# RoboSim_top_level.net
KiCad netlist of a schematic drawn in EAGLE
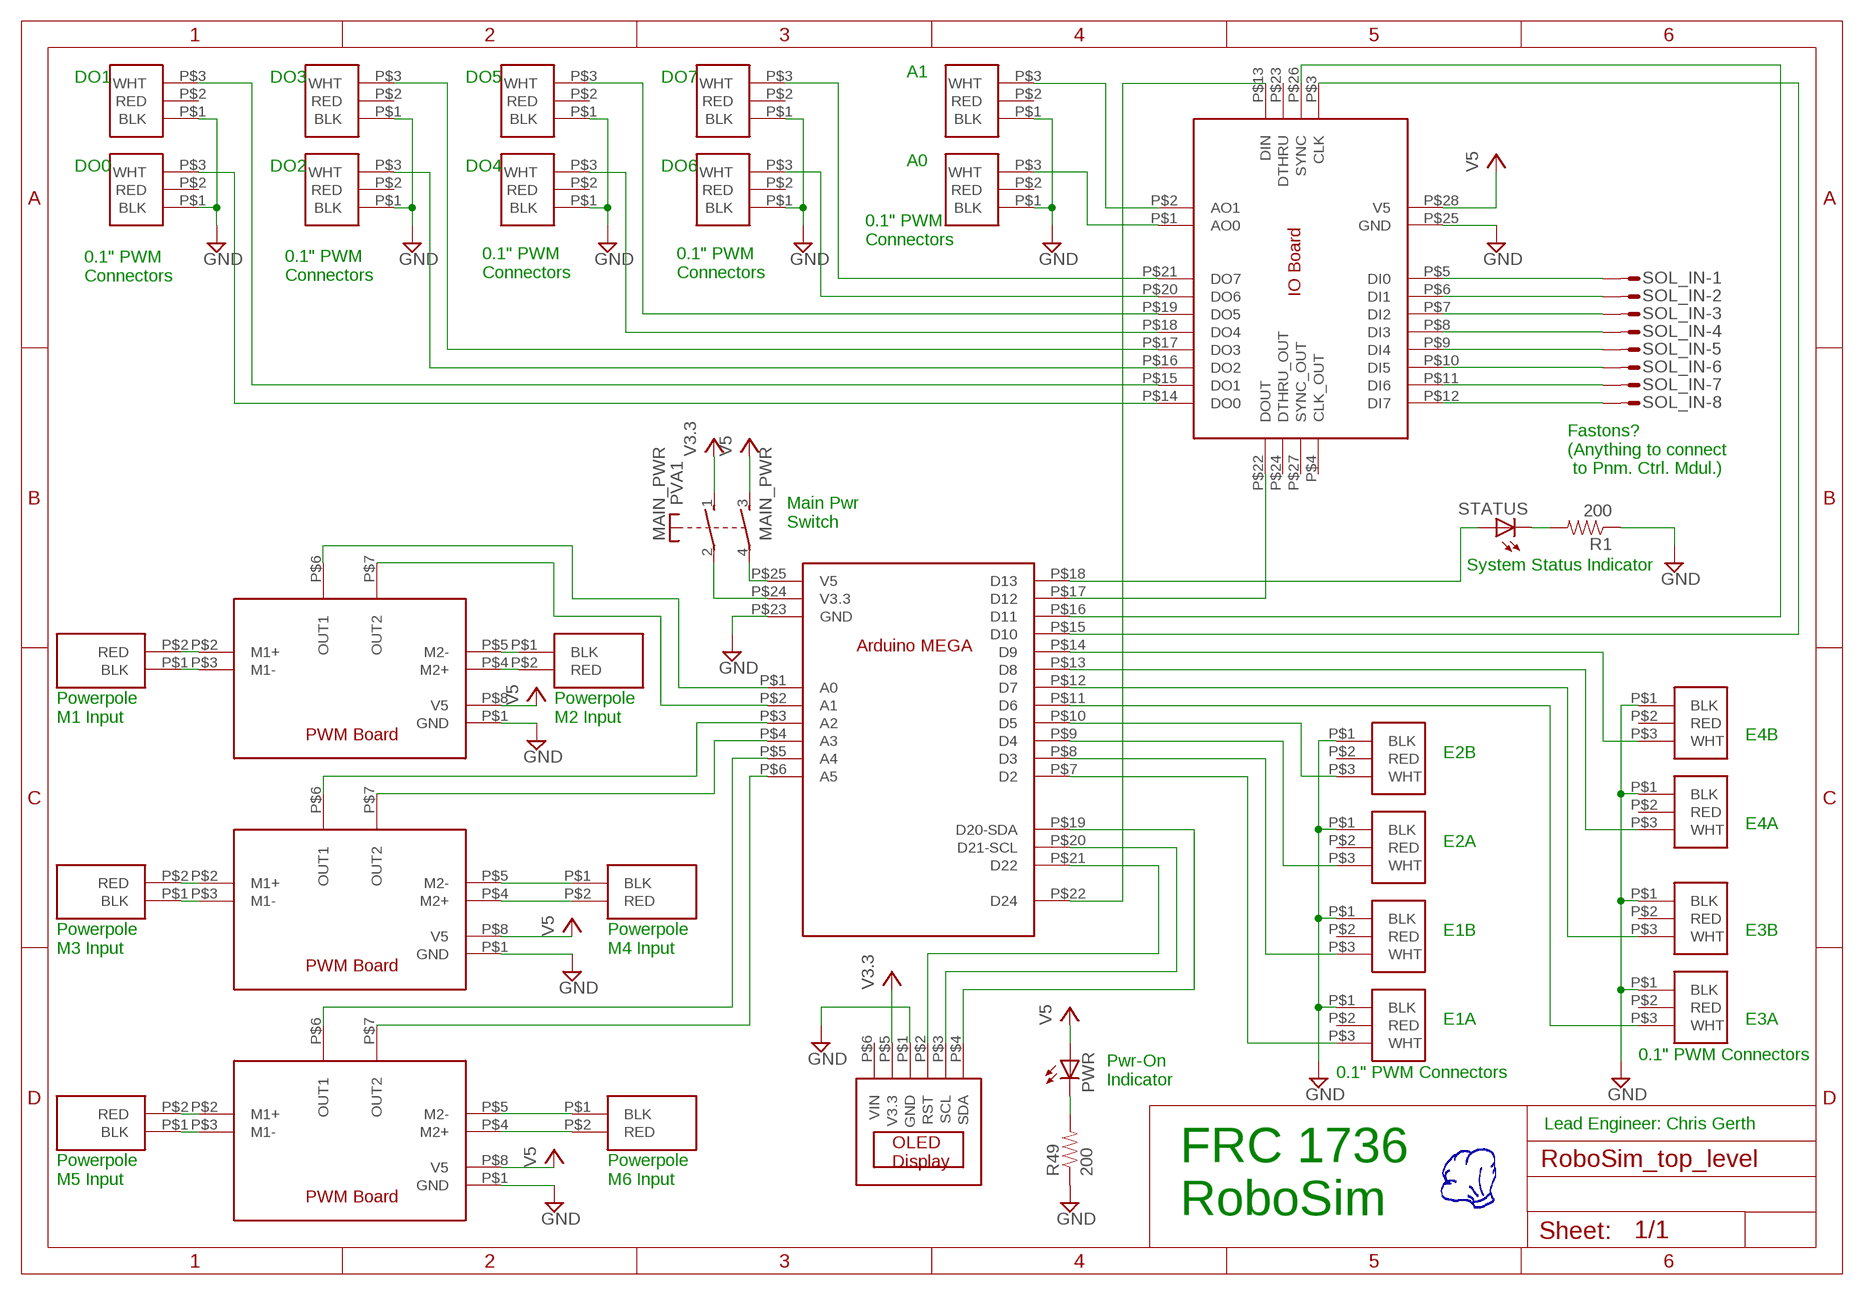
[diagram p0: schematic, sheet 1]

(export (version "E")
  (design (tool "Eeschema 10.0.6"))
  (components
    (comp (ref "MAIN_PWR")
      (value "PVA1")
      (footprint "eagle-import:PVA1F")
      (libsource (lib "eagle-import") (part "PVA1"))
    )
    (comp (ref "PWR")
      (value "LED5MM")
      (footprint "eagle-import:LED5MM")
      (libsource (lib "eagle-import") (part "LED5MM"))
    )
    (comp (ref "R1")
      (value "200")
      (footprint "eagle-import:AXIAL-0.1")
      (libsource (lib "eagle-import") (part "RESISTORPTH-1/4W-VERT"))
    )
    (comp (ref "R49")
      (value "200")
      (footprint "eagle-import:AXIAL-0.1")
      (libsource (lib "eagle-import") (part "RESISTORPTH-1/4W-VERT"))
    )
    (comp (ref "SOL_IN")
      (value "MT6-8")
      (footprint "eagle-import:MT6-8")
      (libsource (lib "eagle-import") (part "MT6-8"))
    )
    (comp (ref "STATUS")
      (value "LED5MM")
      (footprint "eagle-import:LED5MM")
      (libsource (lib "eagle-import") (part "LED5MM"))
    )
    (comp (ref "U$1")
      (value "ARDUINO_MEGA")
      (footprint "eagle-import:DUMMY")
      (libsource (lib "eagle-import") (part "ARDUINO_MEGA"))
    )
    (comp (ref "U$2")
      (value "DISPLAY")
      (footprint "eagle-import:DUMMY")
      (libsource (lib "eagle-import") (part "DISPLAY"))
    )
    (comp (ref "U$3")
      (value "IO_BOARD")
      (footprint "eagle-import:DUMMY")
      (libsource (lib "eagle-import") (part "IO_BOARD"))
    )
    (comp (ref "U$4")
      (value "PWM_BOARD")
      (footprint "eagle-import:DUMMY")
      (libsource (lib "eagle-import") (part "PWM_BOARD"))
    )
    (comp (ref "U$5")
      (value "PWM_BOARD")
      (footprint "eagle-import:DUMMY")
      (libsource (lib "eagle-import") (part "PWM_BOARD"))
    )
    (comp (ref "U$6")
      (value "PWM_BOARD")
      (footprint "eagle-import:DUMMY")
      (libsource (lib "eagle-import") (part "PWM_BOARD"))
    )
    (comp (ref "U$7")
      (value "POWERPOLE")
      (footprint "eagle-import:DUMMY")
      (libsource (lib "eagle-import") (part "POWERPOLE"))
    )
    (comp (ref "U$8")
      (value "POWERPOLE")
      (footprint "eagle-import:DUMMY")
      (libsource (lib "eagle-import") (part "POWERPOLE"))
    )
    (comp (ref "U$9")
      (value "POWERPOLE")
      (footprint "eagle-import:DUMMY")
      (libsource (lib "eagle-import") (part "POWERPOLE"))
    )
    (comp (ref "U$10")
      (value "POWERPOLE")
      (footprint "eagle-import:DUMMY")
      (libsource (lib "eagle-import") (part "POWERPOLE"))
    )
    (comp (ref "U$11")
      (value "POWERPOLE")
      (footprint "eagle-import:DUMMY")
      (libsource (lib "eagle-import") (part "POWERPOLE"))
    )
    (comp (ref "U$12")
      (value "POWERPOLE")
      (footprint "eagle-import:DUMMY")
      (libsource (lib "eagle-import") (part "POWERPOLE"))
    )
    (comp (ref "U$13")
      (value "PWM_CONN")
      (footprint "eagle-import:DUMMY")
      (libsource (lib "eagle-import") (part "PWM_CONN"))
    )
    (comp (ref "U$14")
      (value "PWM_CONN")
      (footprint "eagle-import:DUMMY")
      (libsource (lib "eagle-import") (part "PWM_CONN"))
    )
    (comp (ref "U$15")
      (value "PWM_CONN")
      (footprint "eagle-import:DUMMY")
      (libsource (lib "eagle-import") (part "PWM_CONN"))
    )
    (comp (ref "U$16")
      (value "PWM_CONN")
      (footprint "eagle-import:DUMMY")
      (libsource (lib "eagle-import") (part "PWM_CONN"))
    )
    (comp (ref "U$17")
      (value "PWM_CONN")
      (footprint "eagle-import:DUMMY")
      (libsource (lib "eagle-import") (part "PWM_CONN"))
    )
    (comp (ref "U$18")
      (value "PWM_CONN")
      (footprint "eagle-import:DUMMY")
      (libsource (lib "eagle-import") (part "PWM_CONN"))
    )
    (comp (ref "U$19")
      (value "PWM_CONN")
      (footprint "eagle-import:DUMMY")
      (libsource (lib "eagle-import") (part "PWM_CONN"))
    )
    (comp (ref "U$20")
      (value "PWM_CONN")
      (footprint "eagle-import:DUMMY")
      (libsource (lib "eagle-import") (part "PWM_CONN"))
    )
    (comp (ref "U$21")
      (value "PWM_CONN")
      (footprint "eagle-import:DUMMY")
      (libsource (lib "eagle-import") (part "PWM_CONN"))
    )
    (comp (ref "U$22")
      (value "PWM_CONN")
      (footprint "eagle-import:DUMMY")
      (libsource (lib "eagle-import") (part "PWM_CONN"))
    )
    (comp (ref "U$23")
      (value "PWM_CONN")
      (footprint "eagle-import:DUMMY")
      (libsource (lib "eagle-import") (part "PWM_CONN"))
    )
    (comp (ref "U$24")
      (value "PWM_CONN")
      (footprint "eagle-import:DUMMY")
      (libsource (lib "eagle-import") (part "PWM_CONN"))
    )
    (comp (ref "U$26")
      (value "PWM_CONN")
      (footprint "eagle-import:DUMMY")
      (libsource (lib "eagle-import") (part "PWM_CONN"))
    )
    (comp (ref "U$27")
      (value "PWM_CONN")
      (footprint "eagle-import:DUMMY")
      (libsource (lib "eagle-import") (part "PWM_CONN"))
    )
    (comp (ref "U$28")
      (value "PWM_CONN")
      (footprint "eagle-import:DUMMY")
      (libsource (lib "eagle-import") (part "PWM_CONN"))
    )
    (comp (ref "U$29")
      (value "PWM_CONN")
      (footprint "eagle-import:DUMMY")
      (libsource (lib "eagle-import") (part "PWM_CONN"))
    )
    (comp (ref "U$30")
      (value "PWM_CONN")
      (footprint "eagle-import:DUMMY")
      (libsource (lib "eagle-import") (part "PWM_CONN"))
    )
    (comp (ref "U$31")
      (value "PWM_CONN")
      (footprint "eagle-import:DUMMY")
      (libsource (lib "eagle-import") (part "PWM_CONN"))
    )
  )
  (nets
    (net (code "1") (name "GND") (class "Default")
      (node (ref "R1") (pin "P$1") (pinfunction "1_P$1") (pintype "passive"))
      (node (ref "R49") (pin "P$1") (pinfunction "1_P$1") (pintype "passive"))
      (node (ref "U$1") (pin "P$23") (pinfunction "GND_P$23") (pintype "bidirectional"))
      (node (ref "U$13") (pin "P$1") (pinfunction "BLK_P$1") (pintype "bidirectional"))
      (node (ref "U$14") (pin "P$1") (pinfunction "BLK_P$1") (pintype "bidirectional"))
      (node (ref "U$15") (pin "P$1") (pinfunction "BLK_P$1") (pintype "bidirectional"))
      (node (ref "U$16") (pin "P$1") (pinfunction "BLK_P$1") (pintype "bidirectional"))
      (node (ref "U$17") (pin "P$1") (pinfunction "BLK_P$1") (pintype "bidirectional"))
      (node (ref "U$18") (pin "P$1") (pinfunction "BLK_P$1") (pintype "bidirectional"))
      (node (ref "U$19") (pin "P$1") (pinfunction "BLK_P$1") (pintype "bidirectional"))
      (node (ref "U$2") (pin "P$1") (pinfunction "GND_P$1") (pintype "bidirectional"))
      (node (ref "U$20") (pin "P$1") (pinfunction "BLK_P$1") (pintype "bidirectional"))
      (node (ref "U$21") (pin "P$1") (pinfunction "BLK_P$1") (pintype "bidirectional"))
      (node (ref "U$22") (pin "P$1") (pinfunction "BLK_P$1") (pintype "bidirectional"))
      (node (ref "U$23") (pin "P$1") (pinfunction "BLK_P$1") (pintype "bidirectional"))
      (node (ref "U$24") (pin "P$1") (pinfunction "BLK_P$1") (pintype "bidirectional"))
      (node (ref "U$26") (pin "P$1") (pinfunction "BLK_P$1") (pintype "bidirectional"))
      (node (ref "U$27") (pin "P$1") (pinfunction "BLK_P$1") (pintype "bidirectional"))
      (node (ref "U$28") (pin "P$1") (pinfunction "BLK_P$1") (pintype "bidirectional"))
      (node (ref "U$29") (pin "P$1") (pinfunction "BLK_P$1") (pintype "bidirectional"))
      (node (ref "U$3") (pin "P$25") (pinfunction "GND_P$25") (pintype "bidirectional"))
      (node (ref "U$30") (pin "P$1") (pinfunction "BLK_P$1") (pintype "bidirectional"))
      (node (ref "U$31") (pin "P$1") (pinfunction "BLK_P$1") (pintype "bidirectional"))
      (node (ref "U$4") (pin "P$1") (pinfunction "GND_P$1") (pintype "bidirectional"))
      (node (ref "U$5") (pin "P$1") (pinfunction "GND_P$1") (pintype "bidirectional"))
      (node (ref "U$6") (pin "P$1") (pinfunction "GND_P$1") (pintype "bidirectional"))
    )
    (net (code "2") (name "Net-(MAIN_PWRA-P)") (class "Default")
      (node (ref "MAIN_PWR") (pin "2") (pinfunction "P_2") (pintype "passive"))
      (node (ref "U$1") (pin "P$24") (pinfunction "V3.3_P$24") (pintype "bidirectional"))
    )
    (net (code "3") (name "Net-(MAIN_PWRB-P)") (class "Default")
      (node (ref "MAIN_PWR") (pin "4") (pinfunction "P_4") (pintype "passive"))
      (node (ref "U$1") (pin "P$25") (pinfunction "V5_P$25") (pintype "bidirectional"))
    )
    (net (code "4") (name "Net-(PWR-C)") (class "Default")
      (node (ref "PWR") (pin "K") (pinfunction "C_K") (pintype "passive"))
      (node (ref "R49") (pin "P$2") (pinfunction "2_P$2") (pintype "passive"))
    )
    (net (code "5") (name "Net-(R1-2)") (class "Default")
      (node (ref "R1") (pin "P$2") (pinfunction "2_P$2") (pintype "passive"))
      (node (ref "STATUS") (pin "K") (pinfunction "C_K") (pintype "passive"))
    )
    (net (code "6") (name "Net-(SOL_INA-S)") (class "Default")
      (node (ref "SOL_IN") (pin "1") (pinfunction "S_1") (pintype "passive"))
      (node (ref "U$3") (pin "P$5") (pinfunction "DI0_P$5") (pintype "bidirectional"))
    )
    (net (code "7") (name "Net-(SOL_INB-S)") (class "Default")
      (node (ref "SOL_IN") (pin "2") (pinfunction "S_2") (pintype "passive"))
      (node (ref "U$3") (pin "P$6") (pinfunction "DI1_P$6") (pintype "bidirectional"))
    )
    (net (code "8") (name "Net-(SOL_INC-S)") (class "Default")
      (node (ref "SOL_IN") (pin "3") (pinfunction "S_3") (pintype "passive"))
      (node (ref "U$3") (pin "P$7") (pinfunction "DI2_P$7") (pintype "bidirectional"))
    )
    (net (code "9") (name "Net-(SOL_IND-S)") (class "Default")
      (node (ref "SOL_IN") (pin "4") (pinfunction "S_4") (pintype "passive"))
      (node (ref "U$3") (pin "P$8") (pinfunction "DI3_P$8") (pintype "bidirectional"))
    )
    (net (code "10") (name "Net-(SOL_INE-S)") (class "Default")
      (node (ref "SOL_IN") (pin "5") (pinfunction "S_5") (pintype "passive"))
      (node (ref "U$3") (pin "P$9") (pinfunction "DI4_P$9") (pintype "bidirectional"))
    )
    (net (code "11") (name "Net-(SOL_INF-S)") (class "Default")
      (node (ref "SOL_IN") (pin "6") (pinfunction "S_6") (pintype "passive"))
      (node (ref "U$3") (pin "P$10") (pinfunction "DI5_P$10") (pintype "bidirectional"))
    )
    (net (code "12") (name "Net-(SOL_ING-S)") (class "Default")
      (node (ref "SOL_IN") (pin "7") (pinfunction "S_7") (pintype "passive"))
      (node (ref "U$3") (pin "P$11") (pinfunction "DI6_P$11") (pintype "bidirectional"))
    )
    (net (code "13") (name "Net-(SOL_INH-S)") (class "Default")
      (node (ref "SOL_IN") (pin "8") (pinfunction "S_8") (pintype "passive"))
      (node (ref "U$3") (pin "P$12") (pinfunction "DI7_P$12") (pintype "bidirectional"))
    )
    (net (code "14") (name "Net-(U$1-A0)") (class "Default")
      (node (ref "U$1") (pin "P$1") (pinfunction "A0_P$1") (pintype "bidirectional"))
      (node (ref "U$4") (pin "P$6") (pinfunction "OUT1_P$6") (pintype "bidirectional"))
    )
    (net (code "15") (name "Net-(U$1-A1)") (class "Default")
      (node (ref "U$1") (pin "P$2") (pinfunction "A1_P$2") (pintype "bidirectional"))
      (node (ref "U$4") (pin "P$7") (pinfunction "OUT2_P$7") (pintype "bidirectional"))
    )
    (net (code "16") (name "Net-(U$1-A2)") (class "Default")
      (node (ref "U$1") (pin "P$3") (pinfunction "A2_P$3") (pintype "bidirectional"))
      (node (ref "U$5") (pin "P$6") (pinfunction "OUT1_P$6") (pintype "bidirectional"))
    )
    (net (code "17") (name "Net-(U$1-A3)") (class "Default")
      (node (ref "U$1") (pin "P$4") (pinfunction "A3_P$4") (pintype "bidirectional"))
      (node (ref "U$5") (pin "P$7") (pinfunction "OUT2_P$7") (pintype "bidirectional"))
    )
    (net (code "18") (name "Net-(U$1-A4)") (class "Default")
      (node (ref "U$1") (pin "P$5") (pinfunction "A4_P$5") (pintype "bidirectional"))
      (node (ref "U$6") (pin "P$6") (pinfunction "OUT1_P$6") (pintype "bidirectional"))
    )
    (net (code "19") (name "Net-(U$1-A5)") (class "Default")
      (node (ref "U$1") (pin "P$6") (pinfunction "A5_P$6") (pintype "bidirectional"))
      (node (ref "U$6") (pin "P$7") (pinfunction "OUT2_P$7") (pintype "bidirectional"))
    )
    (net (code "20") (name "Net-(U$1-D2)") (class "Default")
      (node (ref "U$1") (pin "P$7") (pinfunction "D2_P$7") (pintype "bidirectional"))
      (node (ref "U$17") (pin "P$3") (pinfunction "WHT_P$3") (pintype "bidirectional"))
    )
    (net (code "21") (name "Net-(U$1-D3)") (class "Default")
      (node (ref "U$1") (pin "P$8") (pinfunction "D3_P$8") (pintype "bidirectional"))
      (node (ref "U$16") (pin "P$3") (pinfunction "WHT_P$3") (pintype "bidirectional"))
    )
    (net (code "22") (name "Net-(U$1-D4)") (class "Default")
      (node (ref "U$1") (pin "P$9") (pinfunction "D4_P$9") (pintype "bidirectional"))
      (node (ref "U$15") (pin "P$3") (pinfunction "WHT_P$3") (pintype "bidirectional"))
    )
    (net (code "23") (name "Net-(U$1-D5)") (class "Default")
      (node (ref "U$1") (pin "P$10") (pinfunction "D5_P$10") (pintype "bidirectional"))
      (node (ref "U$14") (pin "P$3") (pinfunction "WHT_P$3") (pintype "bidirectional"))
    )
    (net (code "24") (name "Net-(U$1-D6)") (class "Default")
      (node (ref "U$1") (pin "P$11") (pinfunction "D6_P$11") (pintype "bidirectional"))
      (node (ref "U$19") (pin "P$3") (pinfunction "WHT_P$3") (pintype "bidirectional"))
    )
    (net (code "25") (name "Net-(U$1-D7)") (class "Default")
      (node (ref "U$1") (pin "P$12") (pinfunction "D7_P$12") (pintype "bidirectional"))
      (node (ref "U$18") (pin "P$3") (pinfunction "WHT_P$3") (pintype "bidirectional"))
    )
    (net (code "26") (name "Net-(U$1-D8)") (class "Default")
      (node (ref "U$1") (pin "P$13") (pinfunction "D8_P$13") (pintype "bidirectional"))
      (node (ref "U$20") (pin "P$3") (pinfunction "WHT_P$3") (pintype "bidirectional"))
    )
    (net (code "27") (name "Net-(U$1-D9)") (class "Default")
      (node (ref "U$1") (pin "P$14") (pinfunction "D9_P$14") (pintype "bidirectional"))
      (node (ref "U$13") (pin "P$3") (pinfunction "WHT_P$3") (pintype "bidirectional"))
    )
    (net (code "28") (name "Net-(U$1-D10)") (class "Default")
      (node (ref "U$1") (pin "P$15") (pinfunction "D10_P$15") (pintype "bidirectional"))
      (node (ref "U$3") (pin "P$3") (pinfunction "CLK_P$3") (pintype "bidirectional"))
    )
    (net (code "29") (name "Net-(U$1-D11)") (class "Default")
      (node (ref "U$1") (pin "P$16") (pinfunction "D11_P$16") (pintype "bidirectional"))
      (node (ref "U$3") (pin "P$26") (pinfunction "SYNC_P$26") (pintype "bidirectional"))
    )
    (net (code "30") (name "Net-(U$1-D12)") (class "Default")
      (node (ref "U$1") (pin "P$17") (pinfunction "D12_P$17") (pintype "bidirectional"))
      (node (ref "U$3") (pin "P$22") (pinfunction "DOUT_P$22") (pintype "bidirectional"))
    )
    (net (code "31") (name "Net-(U$1-D13)") (class "Default")
      (node (ref "STATUS") (pin "A") (pinfunction "A_A") (pintype "passive"))
      (node (ref "U$1") (pin "P$18") (pinfunction "D13_P$18") (pintype "bidirectional"))
    )
    (net (code "32") (name "Net-(U$1-D20-SDA)") (class "Default")
      (node (ref "U$1") (pin "P$19") (pinfunction "D20-SDA_P$19") (pintype "bidirectional"))
      (node (ref "U$2") (pin "P$4") (pinfunction "SDA_P$4") (pintype "bidirectional"))
    )
    (net (code "33") (name "Net-(U$1-D21-SCL)") (class "Default")
      (node (ref "U$1") (pin "P$20") (pinfunction "D21-SCL_P$20") (pintype "bidirectional"))
      (node (ref "U$2") (pin "P$3") (pinfunction "SCL_P$3") (pintype "bidirectional"))
    )
    (net (code "34") (name "Net-(U$1-D22)") (class "Default")
      (node (ref "U$1") (pin "P$21") (pinfunction "D22_P$21") (pintype "bidirectional"))
      (node (ref "U$2") (pin "P$2") (pinfunction "RST_P$2") (pintype "bidirectional"))
    )
    (net (code "35") (name "Net-(U$1-D24)") (class "Default")
      (node (ref "U$1") (pin "P$22") (pinfunction "D24_P$22") (pintype "bidirectional"))
      (node (ref "U$3") (pin "P$13") (pinfunction "DIN_P$13") (pintype "bidirectional"))
    )
    (net (code "36") (name "Net-(U$3-DO0)") (class "Default")
      (node (ref "U$3") (pin "P$14") (pinfunction "DO0_P$14") (pintype "bidirectional"))
      (node (ref "U$31") (pin "P$3") (pinfunction "WHT_P$3") (pintype "bidirectional"))
    )
    (net (code "37") (name "Net-(U$3-DO1)") (class "Default")
      (node (ref "U$3") (pin "P$15") (pinfunction "DO1_P$15") (pintype "bidirectional"))
      (node (ref "U$30") (pin "P$3") (pinfunction "WHT_P$3") (pintype "bidirectional"))
    )
    (net (code "38") (name "Net-(U$4-M1+)") (class "Default")
      (node (ref "U$4") (pin "P$2") (pinfunction "M1+_P$2") (pintype "bidirectional"))
      (node (ref "U$9") (pin "P$2") (pinfunction "RED_P$2") (pintype "bidirectional"))
    )
    (net (code "39") (name "Net-(U$4-M1-)") (class "Default")
      (node (ref "U$4") (pin "P$3") (pinfunction "M1-_P$3") (pintype "bidirectional"))
      (node (ref "U$9") (pin "P$1") (pinfunction "BLK_P$1") (pintype "bidirectional"))
    )
    (net (code "40") (name "Net-(U$5-M1+)") (class "Default")
      (node (ref "U$5") (pin "P$2") (pinfunction "M1+_P$2") (pintype "bidirectional"))
      (node (ref "U$8") (pin "P$2") (pinfunction "RED_P$2") (pintype "bidirectional"))
    )
    (net (code "41") (name "Net-(U$5-M1-)") (class "Default")
      (node (ref "U$5") (pin "P$3") (pinfunction "M1-_P$3") (pintype "bidirectional"))
      (node (ref "U$8") (pin "P$1") (pinfunction "BLK_P$1") (pintype "bidirectional"))
    )
    (net (code "42") (name "Net-(U$6-M1+)") (class "Default")
      (node (ref "U$6") (pin "P$2") (pinfunction "M1+_P$2") (pintype "bidirectional"))
      (node (ref "U$7") (pin "P$2") (pinfunction "RED_P$2") (pintype "bidirectional"))
    )
    (net (code "43") (name "Net-(U$6-M1-)") (class "Default")
      (node (ref "U$6") (pin "P$3") (pinfunction "M1-_P$3") (pintype "bidirectional"))
      (node (ref "U$7") (pin "P$1") (pinfunction "BLK_P$1") (pintype "bidirectional"))
    )
    (net (code "44") (name "Net-(U$10-BLK)") (class "Default")
      (node (ref "U$10") (pin "P$1") (pinfunction "BLK_P$1") (pintype "bidirectional"))
      (node (ref "U$4") (pin "P$5") (pinfunction "M2-_P$5") (pintype "bidirectional"))
    )
    (net (code "45") (name "Net-(U$10-RED)") (class "Default")
      (node (ref "U$10") (pin "P$2") (pinfunction "RED_P$2") (pintype "bidirectional"))
      (node (ref "U$4") (pin "P$4") (pinfunction "M2+_P$4") (pintype "bidirectional"))
    )
    (net (code "46") (name "Net-(U$11-BLK)") (class "Default")
      (node (ref "U$11") (pin "P$1") (pinfunction "BLK_P$1") (pintype "bidirectional"))
      (node (ref "U$5") (pin "P$5") (pinfunction "M2-_P$5") (pintype "bidirectional"))
    )
    (net (code "47") (name "Net-(U$11-RED)") (class "Default")
      (node (ref "U$11") (pin "P$2") (pinfunction "RED_P$2") (pintype "bidirectional"))
      (node (ref "U$5") (pin "P$4") (pinfunction "M2+_P$4") (pintype "bidirectional"))
    )
    (net (code "48") (name "Net-(U$12-BLK)") (class "Default")
      (node (ref "U$12") (pin "P$1") (pinfunction "BLK_P$1") (pintype "bidirectional"))
      (node (ref "U$6") (pin "P$5") (pinfunction "M2-_P$5") (pintype "bidirectional"))
    )
    (net (code "49") (name "Net-(U$12-RED)") (class "Default")
      (node (ref "U$12") (pin "P$2") (pinfunction "RED_P$2") (pintype "bidirectional"))
      (node (ref "U$6") (pin "P$4") (pinfunction "M2+_P$4") (pintype "bidirectional"))
    )
    (net (code "50") (name "Net-(U$21-WHT)") (class "Default")
      (node (ref "U$21") (pin "P$3") (pinfunction "WHT_P$3") (pintype "bidirectional"))
      (node (ref "U$3") (pin "P$1") (pinfunction "AO0_P$1") (pintype "bidirectional"))
    )
    (net (code "51") (name "Net-(U$22-WHT)") (class "Default")
      (node (ref "U$22") (pin "P$3") (pinfunction "WHT_P$3") (pintype "bidirectional"))
      (node (ref "U$3") (pin "P$2") (pinfunction "AO1_P$2") (pintype "bidirectional"))
    )
    (net (code "52") (name "Net-(U$23-WHT)") (class "Default")
      (node (ref "U$23") (pin "P$3") (pinfunction "WHT_P$3") (pintype "bidirectional"))
      (node (ref "U$3") (pin "P$21") (pinfunction "DO7_P$21") (pintype "bidirectional"))
    )
    (net (code "53") (name "Net-(U$24-WHT)") (class "Default")
      (node (ref "U$24") (pin "P$3") (pinfunction "WHT_P$3") (pintype "bidirectional"))
      (node (ref "U$3") (pin "P$20") (pinfunction "DO6_P$20") (pintype "bidirectional"))
    )
    (net (code "54") (name "Net-(U$26-WHT)") (class "Default")
      (node (ref "U$26") (pin "P$3") (pinfunction "WHT_P$3") (pintype "bidirectional"))
      (node (ref "U$3") (pin "P$19") (pinfunction "DO5_P$19") (pintype "bidirectional"))
    )
    (net (code "55") (name "Net-(U$27-WHT)") (class "Default")
      (node (ref "U$27") (pin "P$3") (pinfunction "WHT_P$3") (pintype "bidirectional"))
      (node (ref "U$3") (pin "P$18") (pinfunction "DO4_P$18") (pintype "bidirectional"))
    )
    (net (code "56") (name "Net-(U$28-WHT)") (class "Default")
      (node (ref "U$28") (pin "P$3") (pinfunction "WHT_P$3") (pintype "bidirectional"))
      (node (ref "U$3") (pin "P$17") (pinfunction "DO3_P$17") (pintype "bidirectional"))
    )
    (net (code "57") (name "Net-(U$29-WHT)") (class "Default")
      (node (ref "U$29") (pin "P$3") (pinfunction "WHT_P$3") (pintype "bidirectional"))
      (node (ref "U$3") (pin "P$16") (pinfunction "DO2_P$16") (pintype "bidirectional"))
    )
    (net (code "58") (name "V3.3") (class "Default")
      (node (ref "MAIN_PWR") (pin "1") (pinfunction "S_1") (pintype "passive"))
      (node (ref "MAIN_PWR") (pin "3") (pinfunction "S_3") (pintype "passive"))
      (node (ref "PWR") (pin "A") (pinfunction "A_A") (pintype "passive"))
      (node (ref "U$2") (pin "P$5") (pinfunction "V3.3_P$5") (pintype "bidirectional"))
      (node (ref "U$3") (pin "P$28") (pinfunction "V5_P$28") (pintype "bidirectional"))
      (node (ref "U$4") (pin "P$8") (pinfunction "V5_P$8") (pintype "bidirectional"))
      (node (ref "U$5") (pin "P$8") (pinfunction "V5_P$8") (pintype "bidirectional"))
      (node (ref "U$6") (pin "P$8") (pinfunction "V5_P$8") (pintype "bidirectional"))
    )
    (net (code "59") (name "unconnected-(U$2-VIN-PadP$6)") (class "Default")
      (node (ref "U$2") (pin "P$6") (pinfunction "VIN_P$6") (pintype "bidirectional"))
    )
    (net (code "60") (name "unconnected-(U$3-CLK_OUT-PadP$4)") (class "Default")
      (node (ref "U$3") (pin "P$4") (pinfunction "CLK_OUT_P$4") (pintype "bidirectional"))
    )
    (net (code "61") (name "unconnected-(U$3-DTHRU-PadP$23)") (class "Default")
      (node (ref "U$3") (pin "P$23") (pinfunction "DTHRU_P$23") (pintype "bidirectional"))
    )
    (net (code "62") (name "unconnected-(U$3-DTHRU_OUT-PadP$24)") (class "Default")
      (node (ref "U$3") (pin "P$24") (pinfunction "DTHRU_OUT_P$24") (pintype "bidirectional"))
    )
    (net (code "63") (name "unconnected-(U$3-SYNC_OUT-PadP$27)") (class "Default")
      (node (ref "U$3") (pin "P$27") (pinfunction "SYNC_OUT_P$27") (pintype "bidirectional"))
    )
    (net (code "64") (name "unconnected-(U$13-RED-PadP$2)") (class "Default")
      (node (ref "U$13") (pin "P$2") (pinfunction "RED_P$2") (pintype "bidirectional"))
    )
    (net (code "65") (name "unconnected-(U$14-RED-PadP$2)") (class "Default")
      (node (ref "U$14") (pin "P$2") (pinfunction "RED_P$2") (pintype "bidirectional"))
    )
    (net (code "66") (name "unconnected-(U$15-RED-PadP$2)") (class "Default")
      (node (ref "U$15") (pin "P$2") (pinfunction "RED_P$2") (pintype "bidirectional"))
    )
    (net (code "67") (name "unconnected-(U$16-RED-PadP$2)") (class "Default")
      (node (ref "U$16") (pin "P$2") (pinfunction "RED_P$2") (pintype "bidirectional"))
    )
    (net (code "68") (name "unconnected-(U$17-RED-PadP$2)") (class "Default")
      (node (ref "U$17") (pin "P$2") (pinfunction "RED_P$2") (pintype "bidirectional"))
    )
    (net (code "69") (name "unconnected-(U$18-RED-PadP$2)") (class "Default")
      (node (ref "U$18") (pin "P$2") (pinfunction "RED_P$2") (pintype "bidirectional"))
    )
    (net (code "70") (name "unconnected-(U$19-RED-PadP$2)") (class "Default")
      (node (ref "U$19") (pin "P$2") (pinfunction "RED_P$2") (pintype "bidirectional"))
    )
    (net (code "71") (name "unconnected-(U$20-RED-PadP$2)") (class "Default")
      (node (ref "U$20") (pin "P$2") (pinfunction "RED_P$2") (pintype "bidirectional"))
    )
    (net (code "72") (name "unconnected-(U$21-RED-PadP$2)") (class "Default")
      (node (ref "U$21") (pin "P$2") (pinfunction "RED_P$2") (pintype "bidirectional"))
    )
    (net (code "73") (name "unconnected-(U$22-RED-PadP$2)") (class "Default")
      (node (ref "U$22") (pin "P$2") (pinfunction "RED_P$2") (pintype "bidirectional"))
    )
    (net (code "74") (name "unconnected-(U$23-RED-PadP$2)") (class "Default")
      (node (ref "U$23") (pin "P$2") (pinfunction "RED_P$2") (pintype "bidirectional"))
    )
    (net (code "75") (name "unconnected-(U$24-RED-PadP$2)") (class "Default")
      (node (ref "U$24") (pin "P$2") (pinfunction "RED_P$2") (pintype "bidirectional"))
    )
    (net (code "76") (name "unconnected-(U$26-RED-PadP$2)") (class "Default")
      (node (ref "U$26") (pin "P$2") (pinfunction "RED_P$2") (pintype "bidirectional"))
    )
    (net (code "77") (name "unconnected-(U$27-RED-PadP$2)") (class "Default")
      (node (ref "U$27") (pin "P$2") (pinfunction "RED_P$2") (pintype "bidirectional"))
    )
    (net (code "78") (name "unconnected-(U$28-RED-PadP$2)") (class "Default")
      (node (ref "U$28") (pin "P$2") (pinfunction "RED_P$2") (pintype "bidirectional"))
    )
    (net (code "79") (name "unconnected-(U$29-RED-PadP$2)") (class "Default")
      (node (ref "U$29") (pin "P$2") (pinfunction "RED_P$2") (pintype "bidirectional"))
    )
    (net (code "80") (name "unconnected-(U$30-RED-PadP$2)") (class "Default")
      (node (ref "U$30") (pin "P$2") (pinfunction "RED_P$2") (pintype "bidirectional"))
    )
    (net (code "81") (name "unconnected-(U$31-RED-PadP$2)") (class "Default")
      (node (ref "U$31") (pin "P$2") (pinfunction "RED_P$2") (pintype "bidirectional"))
    )
  )
)
